# SAMV71_Xplained_Ultra_Power_Supply.net
KiCad netlist of a schematic drawn in Altium Designer
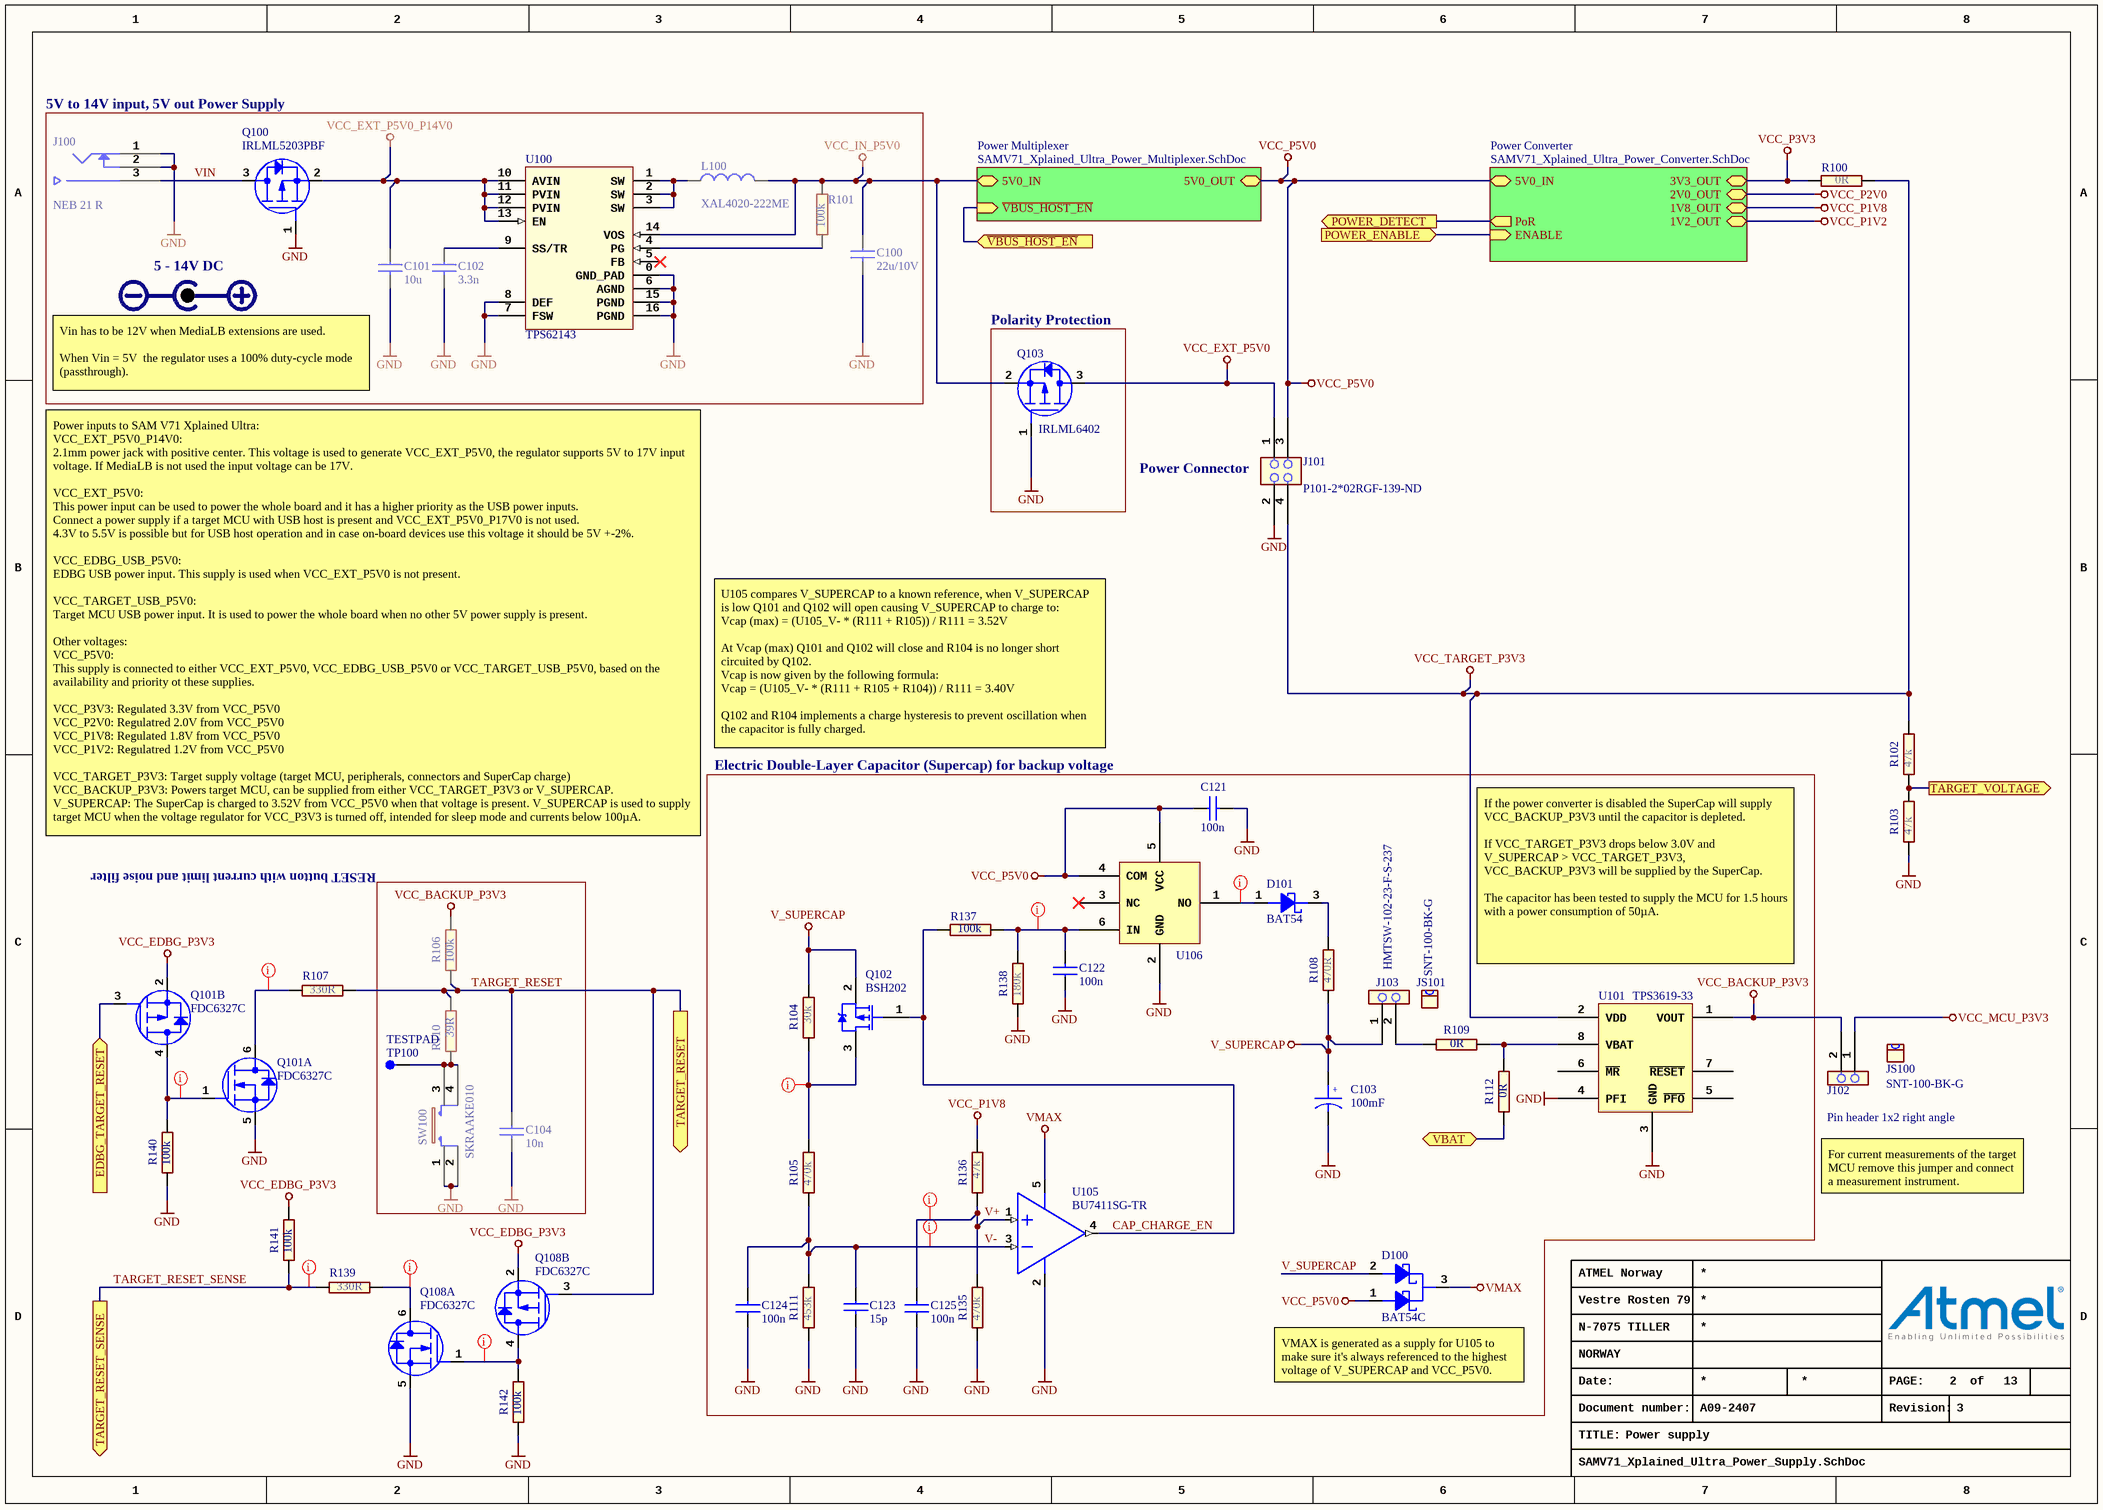
[diagram p0: SAMV71_Xplained_Ultra_Power_Supply.SchDoc]

(export (version "E")
  (design (tool "Eeschema 10.0.6"))
  (components
    (comp (ref "C100")
      (value "22u/10V")
      (footprint "AP1-00003")
      (description "Ceramic capacitor, SMD 0805, X5R, 10V, Â±20%")
      (fields (field (name "MANUFACTURER") "tdk") (field (name "MPN") "C2012X5R1A226M/0.85"))
      (libsource (lib "AltiumDbLib") (part "CAP-NONPOL"))
    )
    (comp (ref "C101")
      (value "10u")
      (footprint "AP1-00003")
      (description "Ceramic capacitor, SMD 0805, X5R, 25V, Â±10%")
      (fields (field (name "TOLERANCE") "Â±10%") (field (name "MANUFACTURER") "Murata"))
      (libsource (lib "AltiumDbLib") (part "CAP-NONPOL"))
    )
    (comp (ref "C102")
      (value "3.3n")
      (footprint "AP1-00001")
      (description "Ceramic capacitor, SMD 0402, X7R, 25V, +/-10%")
      (fields (field (name "TOLERANCE") "25V, +/-10%"))
      (libsource (lib "AltiumDbLib") (part "CAP-NONPOL"))
    )
    (comp (ref "C103")
      (value "100mF")
      (footprint "AP1-00122")
      (description "Electric Double-Layer (Supercapacitor), 100mF, SMD, 10.5mm diameter, 25Î© ESR")
      (fields (field (name "TOLERANCE") "-20/+80%") (field (name "MANUFACTURER") "Kemet"))
      (libsource (lib "AltiumDbLib") (part "CAP-POL"))
    )
    (comp (ref "C104")
      (value "10n")
      (footprint "AP1-00053")
      (description "Ceramic capacitor, SMD 0402, X7R, 25V, +/-10%")
      (fields (field (name "TOLERANCE") "25V, +/-10%"))
      (libsource (lib "AltiumDbLib") (part "CAP-NONPOL"))
    )
    (comp (ref "C121")
      (value "100n")
      (footprint "AP1-00001")
      (description "Ceramic capacitor, SMD 0402, X7R, 16V, +/-10%")
      (fields (field (name "TOLERANCE") "16V, +/-10%") (field (name "MANUFACTURER") "Kemet"))
      (libsource (lib "AltiumDbLib") (part "CAP-NONPOL"))
    )
    (comp (ref "C122")
      (value "100n")
      (footprint "AP1-00053")
      (description "Ceramic capacitor, SMD 0402, X7R, 16V, +/-10%")
      (fields (field (name "TOLERANCE") "16V, +/-10%") (field (name "MANUFACTURER") "Kemet"))
      (libsource (lib "AltiumDbLib") (part "CAP-NONPOL"))
    )
    (comp (ref "C123")
      (value "15p")
      (footprint "AP1-00001")
      (description "Ceramic capacitor, SMD 0402, NP0, 50V, +/-5%")
      (fields (field (name "TOLERANCE") "50V, +/-5%"))
      (libsource (lib "AltiumDbLib") (part "CAP-NONPOL"))
    )
    (comp (ref "C124")
      (value "100n")
      (footprint "AP1-00001")
      (description "Ceramic capacitor, SMD 0402, X7R, 16V, +/-10%")
      (fields (field (name "TOLERANCE") "16V, +/-10%") (field (name "MANUFACTURER") "Kemet"))
      (libsource (lib "AltiumDbLib") (part "CAP-NONPOL"))
    )
    (comp (ref "C125")
      (value "100n")
      (footprint "AP1-00001")
      (description "Ceramic capacitor, SMD 0402, X7R, 16V, +/-10%")
      (fields (field (name "TOLERANCE") "16V, +/-10%") (field (name "MANUFACTURER") "Kemet"))
      (libsource (lib "AltiumDbLib") (part "CAP-NONPOL"))
    )
    (comp (ref "D100")
      (value "BAT54C")
      (footprint "AP5-00002")
      (description "Schottky double Diodes, NXP, SOT23-3")
      (fields (field (name "MANUFACTURER") "NXP"))
      (libsource (lib "AltiumDbLib") (part "DUAL_SCHOTTKY_123"))
    )
    (comp (ref "D101")
      (value "BAT54")
      (footprint "AP4-00007")
      (fields (field (name "MANUFACTURER") "Philips"))
      (libsource (lib "AltiumDbLib") (part "SCHOTTKY_SMD_31"))
    )
    (comp (ref "J100")
      (value "NEB 21 R")
      (footprint "AP8-00853")
      (description "Through hole DC jack 2.1mm, 12V, 3A")
      (fields (field (name "MANUFACTURER") "Lumberg"))
      (libsource (lib "AltiumDbLib") (part "DC_JACK"))
    )
    (comp (ref "J101")
      (value "P101-2*02RGF-139-ND")
      (footprint "AP8-00628")
      (description "Pin header, 2x2, Right Angle, 2.54mm, THT, Pin In Paste")
      (fields (field (name "MANUFACTURER") "Pro-data International Corp"))
      (libsource (lib "AltiumDbLib") (part "HEADER 2x2"))
    )
    (comp (ref "J102")
      (value "Pin header 1x2 right angle")
      (footprint "AP8-00367")
      (description "1x2 pin header, right angle, 2.54 mm pitch, through-hole")
      (fields (field (name "MANUFACTURER") "Pro-data International Corp") (field (name "MPN") "2213R-2G"))
      (libsource (lib "") (part "HEADER 1x2_1"))
    )
    (comp (ref "J103")
      (value "HMTSW-102-23-F-S-237")
      (footprint "AP8-00733")
      (description "1x2 pin header, 2.54mm pitch, Pin-in-Paste THM")
      (fields (field (name "MANUFACTURER") "SAMTEC"))
      (libsource (lib "AltiumDbLib") (part "HEADER 1x2"))
    )
    (comp (ref "JS100")
      (value "SNT-100-BK-G")
      (footprint "AP8-00525")
      (description "Jumper cap for 2.54mm pinheader")
      (fields (field (name "MANUFACTURER") "SAMTEC"))
      (libsource (lib "AltiumDbLib") (part "JUMPER_CAP"))
    )
    (comp (ref "JS101")
      (value "SNT-100-BK-G")
      (footprint "AP8-00525")
      (description "Jumper cap for 2.54mm pinheader")
      (fields (field (name "MANUFACTURER") "SAMTEC"))
      (libsource (lib "AltiumDbLib") (part "JUMPER_CAP"))
    )
    (comp (ref "L100")
      (value "XAL4020-222ME")
      (footprint "AP3-00119")
      (description "2.2ÂµH Shielded Power Inductor, 4x4x2mm, Isat=5.6A , Irms=4.0A , DCR=35.2mÎ©")
      (fields (field (name "TOLERANCE") "20%") (field (name "MANUFACTURER") "Coilcraft"))
      (libsource (lib "AltiumDbLib") (part "INDUCTOR"))
    )
    (comp (ref "Q100")
      (value "IRLML5203PBF")
      (footprint "AP5-00002")
      (fields (field (name "MANUFACTURER") "International Rectifier"))
      (libsource (lib "AltiumDbLib") (part "MOSFET_P_GSD"))
    )
    (comp (ref "Q101")
      (value "FDC6327C")
      (footprint "AP5-00008")
      (fields (field (name "MANUFACTURER") "Fairchild") (field (name "Comment") "Farnell no: 9844856"))
      (libsource (lib "AltiumDbLib") (part "DUAL_NP_G1S2G2D2S1D1"))
    )
    (comp (ref "Q102")
      (value "BSH202")
      (footprint "AP4-00018")
      (description "P-channel Power MOSFET,30V, 520mA continuous drain current")
      (fields (field (name "MANUFACTURER") "NXP"))
      (libsource (lib "AltiumDbLib") (part "BSH202"))
    )
    (comp (ref "Q103")
      (value "IRLML6402")
      (footprint "AP5-00002")
      (description "P-ch. MOSFET. -30V, -3.7A continuous,RDS(ON)=0.05Ohm@VGS=-4,5V, RDS(ON)=0.08Ohm@VGS=-2.5V")
      (fields (field (name "MANUFACTURER") "International Rectifier") (field (name "MPN") "IRLML6402PBF"))
      (libsource (lib "AltiumDbLib") (part "MOSFET_P_GSD"))
    )
    (comp (ref "Q108")
      (value "FDC6327C")
      (footprint "AP5-00008")
      (fields (field (name "MANUFACTURER") "Fairchild") (field (name "Comment") "Farnell no: 9844856"))
      (libsource (lib "AltiumDbLib") (part "DUAL_NP_G1S2G2D2S1D1"))
    )
    (comp (ref "R100")
      (value "0R")
      (footprint "AP2-00000")
      (description "Thick film resistor, SMD 0402, 1/16W, 1%")
      (fields (field (name "TOLERANCE") "1 %") (field (name "MANUFACTURER") "(n/a)"))
      (libsource (lib "") (part "R2_1"))
    )
    (comp (ref "R101")
      (value "100k")
      (footprint "AP2-00000")
      (description "Thick film resistor, SMD 0402, 1/16W, 1%")
      (fields (field (name "TOLERANCE") "1 %"))
      (libsource (lib "") (part "R2_4"))
    )
    (comp (ref "R102")
      (value "47k")
      (footprint "AP2-00000")
      (description "Thick film resistor, SMD 0402, 1/16W, 1%")
      (fields (field (name "TOLERANCE") "1 %"))
      (libsource (lib "") (part "R2_3"))
    )
    (comp (ref "R103")
      (value "47k")
      (footprint "AP2-00000")
      (description "Thick film resistor, SMD 0402, 1/16W, 1%")
      (fields (field (name "TOLERANCE") "1 %"))
      (libsource (lib "") (part "R2_3"))
    )
    (comp (ref "R104")
      (value "30k")
      (footprint "AP2-00000")
      (description "Thick film resistor, SMD 0402, 1/16W, 1%")
      (fields (field (name "TOLERANCE") "1 %"))
      (libsource (lib "AltiumDbLib") (part "R2"))
    )
    (comp (ref "R105")
      (value "470k")
      (footprint "AP2-00000")
      (description "Thick film resistor, SMD 0402, 1/16W, 1%")
      (fields (field (name "TOLERANCE") "1 %"))
      (libsource (lib "AltiumDbLib") (part "R2"))
    )
    (comp (ref "R106")
      (value "100k")
      (footprint "AP2-00011")
      (description "Thick film resistor, SMD 0402, 1/16W, 1%")
      (fields (field (name "TOLERANCE") "1 %"))
      (libsource (lib "AltiumDbLib") (part "R2"))
    )
    (comp (ref "R107")
      (value "330R")
      (footprint "AP2-00011")
      (description "Thick film resistor, SMD 0402, 1/16W, 1%")
      (fields (field (name "TOLERANCE") "1 %"))
      (libsource (lib "") (part "R2_1"))
    )
    (comp (ref "R108")
      (value "470R")
      (footprint "AP2-00000")
      (description "Thick film resistor, SMD 0402, 1/16W, 1%")
      (fields (field (name "TOLERANCE") "1 %"))
      (libsource (lib "") (part "R2_4"))
    )
    (comp (ref "R109")
      (value "0R")
      (footprint "AP2-00000")
      (description "RES 0.0 OHM 1/16W 0402 SMD")
      (fields (field (name "TOLERANCE") "1 %") (field (name "MANUFACTURER") "(n/a)"))
      (libsource (lib "") (part "R2_1"))
    )
    (comp (ref "R110")
      (value "39R")
      (footprint "AP2-00011")
      (description "Thick film resistor, SMD 0402, 1/16W, 1%")
      (fields (field (name "TOLERANCE") "1 %"))
      (libsource (lib "") (part "R2_2"))
    )
    (comp (ref "R111")
      (value "453k")
      (footprint "AP2-00000")
      (description "Thick film resistor, SMD 0402, 1/16W, 1%")
      (fields (field (name "TOLERANCE") "1 %"))
      (libsource (lib "AltiumDbLib") (part "R2"))
    )
    (comp (ref "R112")
      (value "0R")
      (footprint "AP2-00000")
      (description "RES 0.0 OHM 1/16W 0402 SMD")
      (fields (field (name "TOLERANCE") "1 %") (field (name "MANUFACTURER") "(n/a)"))
      (libsource (lib "AltiumDbLib") (part "R2"))
    )
    (comp (ref "R135")
      (value "470k")
      (footprint "AP2-00000")
      (description "Thick film resistor, SMD 0402, 1/16W, 1%")
      (fields (field (name "TOLERANCE") "1 %"))
      (libsource (lib "AltiumDbLib") (part "R2"))
    )
    (comp (ref "R136")
      (value "47k")
      (footprint "AP2-00000")
      (description "Thick film resistor, SMD 0402, 1/16W, 1%")
      (fields (field (name "TOLERANCE") "1 %"))
      (libsource (lib "AltiumDbLib") (part "R2"))
    )
    (comp (ref "R137")
      (value "100k")
      (footprint "AP2-00011")
      (description "Thick film resistor, SMD 0402, 1/16W, 1%")
      (fields (field (name "TOLERANCE") "1 %"))
      (libsource (lib "") (part "R2_1"))
    )
    (comp (ref "R138")
      (value "180k")
      (footprint "AP2-00011")
      (description "Thick film resistor, SMD 0402, 1/16W, 1%")
      (fields (field (name "TOLERANCE") "1 %"))
      (libsource (lib "AltiumDbLib") (part "R2"))
    )
    (comp (ref "R139")
      (value "330R")
      (footprint "AP2-00011")
      (description "Thick film resistor, SMD 0402, 1/16W, 1%")
      (fields (field (name "TOLERANCE") "1 %"))
      (libsource (lib "") (part "R2_1"))
    )
    (comp (ref "R140")
      (value "100k")
      (footprint "AP2-00011")
      (description "Thick film resistor, SMD 0402, 1/16W, 1%")
      (fields (field (name "TOLERANCE") "1 %"))
      (libsource (lib "AltiumDbLib") (part "R2"))
    )
    (comp (ref "R141")
      (value "100k")
      (footprint "AP2-00011")
      (description "Thick film resistor, SMD 0402, 1/16W, 1%")
      (fields (field (name "TOLERANCE") "1 %"))
      (libsource (lib "AltiumDbLib") (part "R2"))
    )
    (comp (ref "R142")
      (value "100k")
      (footprint "AP2-00011")
      (description "Thick film resistor, SMD 0402, 1/16W, 1%")
      (fields (field (name "TOLERANCE") "1 %"))
      (libsource (lib "AltiumDbLib") (part "R2"))
    )
    (comp (ref "SW100")
      (value "SKRAAKE010")
      (footprint "AP8-00137")
      (description "6.2x6.2 mm SMD tact switch, same as A08-0091 but less force is needed")
      (fields
        (field (name "MANUFACTURER") "ALPS")
        (field (name "Comment") "Can be ordered in low volumes from Mouser")
      )
      (libsource (lib "AltiumDbLib") (part "PUSHBUTTON1"))
    )
    (comp (ref "TP100")
      (value "TESTPAD")
      (footprint "AP8-00010")
      (description "Single SMD testpad")
      (libsource (lib "AltiumDbLib") (part "TESTPOINT"))
    )
    (comp (ref "U100")
      (value "TPS62143")
      (footprint "AP6-00313")
      (description "5V to 17V in, 5V 2A out, Step-Down Converter")
      (fields (field (name "MANUFACTURER") "Texas Instruments") (field (name "MPN") "TPS62143RGTR"))
      (libsource (lib "AltiumDbLib") (part "TPS62143"))
    )
    (comp (ref "U101")
      (value "TPS3619-33")
      (footprint "AP6-00382")
      (description "Backup battery supervisors for RAM retention")
      (fields (field (name "MANUFACTURER") "Texas Instruments") (field (name "MPN") "TPS3619-33DGK"))
      (libsource (lib "AltiumDbLib") (part "TPS3619"))
    )
    (comp (ref "U105")
      (value "BU7411SG-TR")
      (footprint "AP6-00087")
      (description "Single, Low Voltage (1.6-5.5V), Low Power (0.35ÂµA), low cost")
      (fields (field (name "MANUFACTURER") "ROHM"))
      (libsource (lib "AltiumDbLib") (part "LMV321M5"))
    )
    (comp (ref "U106")
      (value "~")
      (footprint "AP6-00056")
      (description "1.65V to 5.5V SPDT Analog switch")
      (fields (field (name "MANUFACTURER") "Texas Instruments") (field (name "MPN") "TS5A3160DBVR"))
      (libsource (lib "AltiumDbLib") (part "TS5A3160"))
    )
  )
  (nets
    (net (code "1") (name "/CAP_CHARGE_EN") (class "Default")
      (node (ref "Q102") (pin "1") (pinfunction "G_1") (pintype "passive"))
      (node (ref "R137") (pin "1") (pinfunction "1_1") (pintype "passive"))
      (node (ref "U105") (pin "4") (pinfunction "OUT_4") (pintype "output"))
    )
    (net (code "2") (name "/EDBG_TARGET_RESET") (class "Default")
      (node (ref "Q101") (pin "3") (pinfunction "G_3") (pintype "passive"))
    )
    (net (code "5") (name "/TARGET_RESET") (class "Default")
      (node (ref "C104") (pin "1") (pinfunction "1_1") (pintype "passive"))
      (node (ref "Q108") (pin "3") (pinfunction "G_3") (pintype "passive"))
      (node (ref "R106") (pin "1") (pinfunction "1_1") (pintype "passive"))
      (node (ref "R107") (pin "2") (pinfunction "2_2") (pintype "passive"))
      (node (ref "R110") (pin "2") (pinfunction "2_2") (pintype "passive"))
    )
    (net (code "6") (name "/TARGET_RESET_SENSE") (class "Default")
      (node (ref "R139") (pin "1") (pinfunction "1_1") (pintype "passive"))
      (node (ref "R141") (pin "1") (pinfunction "1_1") (pintype "passive"))
    )
    (net (code "7") (name "/TARGET_VOLTAGE") (class "Default")
      (node (ref "R102") (pin "1") (pinfunction "1_1") (pintype "passive"))
      (node (ref "R103") (pin "2") (pinfunction "2_2") (pintype "passive"))
    )
    (net (code "8") (name "/V+") (class "Default")
      (node (ref "C125") (pin "2") (pinfunction "2_2") (pintype "passive"))
      (node (ref "R135") (pin "2") (pinfunction "2_2") (pintype "passive"))
      (node (ref "R136") (pin "1") (pinfunction "1_1") (pintype "passive"))
      (node (ref "U105") (pin "1") (pinfunction "IN+_1") (pintype "input"))
    )
    (net (code "9") (name "/V-") (class "Default")
      (node (ref "C123") (pin "1") (pinfunction "1_1") (pintype "passive"))
      (node (ref "C124") (pin "2") (pinfunction "2_2") (pintype "passive"))
      (node (ref "R105") (pin "1") (pinfunction "1_1") (pintype "passive"))
      (node (ref "R111") (pin "2") (pinfunction "2_2") (pintype "passive"))
      (node (ref "U105") (pin "3") (pinfunction "IN-_3") (pintype "input"))
    )
    (net (code "10") (name "/VBAT") (class "Default")
      (node (ref "R112") (pin "1") (pinfunction "1_1") (pintype "passive"))
    )
    (net (code "11") (name "/VIN") (class "Default")
      (node (ref "J100") (pin "3") (pinfunction "3_3") (pintype "passive"))
      (node (ref "Q100") (pin "3") (pinfunction "D_3") (pintype "passive"))
    )
    (net (code "13") (name "GND") (class "Default")
      (node (ref "C100") (pin "2") (pinfunction "2_2") (pintype "passive"))
      (node (ref "C101") (pin "2") (pinfunction "2_2") (pintype "passive"))
      (node (ref "C102") (pin "2") (pinfunction "2_2") (pintype "passive"))
      (node (ref "C103") (pin "2") (pinfunction "2_2") (pintype "passive"))
      (node (ref "C104") (pin "2") (pinfunction "2_2") (pintype "passive"))
      (node (ref "C121") (pin "2") (pinfunction "2_2") (pintype "passive"))
      (node (ref "C122") (pin "1") (pinfunction "1_1") (pintype "passive"))
      (node (ref "C123") (pin "2") (pinfunction "2_2") (pintype "passive"))
      (node (ref "C124") (pin "1") (pinfunction "1_1") (pintype "passive"))
      (node (ref "C125") (pin "1") (pinfunction "1_1") (pintype "passive"))
      (node (ref "J100") (pin "1") (pinfunction "1_1") (pintype "passive"))
      (node (ref "J100") (pin "2") (pinfunction "2_2") (pintype "passive"))
      (node (ref "J101") (pin "2") (pinfunction "2_2") (pintype "passive"))
      (node (ref "Q100") (pin "1") (pinfunction "G_1") (pintype "passive"))
      (node (ref "Q101") (pin "5") (pinfunction "S_5") (pintype "passive"))
      (node (ref "Q103") (pin "1") (pinfunction "G_1") (pintype "passive"))
      (node (ref "Q108") (pin "5") (pinfunction "S_5") (pintype "passive"))
      (node (ref "R103") (pin "1") (pinfunction "1_1") (pintype "passive"))
      (node (ref "R111") (pin "1") (pinfunction "1_1") (pintype "passive"))
      (node (ref "R135") (pin "1") (pinfunction "1_1") (pintype "passive"))
      (node (ref "R138") (pin "1") (pinfunction "1_1") (pintype "passive"))
      (node (ref "R140") (pin "1") (pinfunction "1_1") (pintype "passive"))
      (node (ref "R142") (pin "1") (pinfunction "1_1") (pintype "passive"))
      (node (ref "SW100") (pin "1") (pinfunction "1_1") (pintype "passive"))
      (node (ref "SW100") (pin "2") (pinfunction "2_2") (pintype "passive"))
      (node (ref "U100") (pin "0") (pinfunction "GND_PAD_0") (pintype "passive"))
      (node (ref "U100") (pin "15") (pinfunction "PGND_15") (pintype "power_in"))
      (node (ref "U100") (pin "16") (pinfunction "PGND_16") (pintype "power_in"))
      (node (ref "U100") (pin "6") (pinfunction "AGND_6") (pintype "power_in"))
      (node (ref "U100") (pin "7") (pinfunction "FSW_7") (pintype "power_in"))
      (node (ref "U100") (pin "8") (pinfunction "DEF_8") (pintype "power_in"))
      (node (ref "U101") (pin "3") (pinfunction "GND_3") (pintype "passive"))
      (node (ref "U101") (pin "4") (pinfunction "PFI_4") (pintype "passive"))
      (node (ref "U105") (pin "2") (pinfunction "GND_2") (pintype "power_in"))
      (node (ref "U106") (pin "2") (pinfunction "GND_2") (pintype "passive"))
    )
    (net (code "14") (name "Net-(D101-ANODE)") (class "Default")
      (node (ref "D101") (pin "1") (pinfunction "ANODE_1") (pintype "passive"))
      (node (ref "U106") (pin "1") (pinfunction "NO_1") (pintype "passive"))
    )
    (net (code "15") (name "Net-(D101-CATHODE)") (class "Default")
      (node (ref "D101") (pin "3") (pinfunction "CATHODE_3") (pintype "passive"))
      (node (ref "R108") (pin "1") (pinfunction "1_1") (pintype "passive"))
    )
    (net (code "16") (name "Net-(J103-Pad2)") (class "Default")
      (node (ref "J103") (pin "2") (pinfunction "2_2") (pintype "passive"))
      (node (ref "R109") (pin "1") (pinfunction "1_1") (pintype "passive"))
    )
    (net (code "17") (name "Net-(L100-Pad1)") (class "Default")
      (node (ref "L100") (pin "1") (pinfunction "1_1") (pintype "passive"))
      (node (ref "U100") (pin "1") (pinfunction "SW_1") (pintype "power_in"))
      (node (ref "U100") (pin "2") (pinfunction "SW_2") (pintype "power_in"))
      (node (ref "U100") (pin "3") (pinfunction "SW_3") (pintype "power_in"))
    )
    (net (code "18") (name "Net-(Q101A-D)") (class "Default")
      (node (ref "Q101") (pin "6") (pinfunction "D_6") (pintype "passive"))
      (node (ref "R107") (pin "1") (pinfunction "1_1") (pintype "passive"))
    )
    (net (code "19") (name "Net-(Q101A-G)") (class "Default")
      (node (ref "Q101") (pin "1") (pinfunction "G_1") (pintype "passive"))
      (node (ref "Q101") (pin "4") (pinfunction "D_4") (pintype "passive"))
      (node (ref "R140") (pin "2") (pinfunction "2_2") (pintype "passive"))
    )
    (net (code "20") (name "Net-(Q102-D)") (class "Default")
      (node (ref "Q102") (pin "3") (pinfunction "D_3") (pintype "passive"))
      (node (ref "R104") (pin "1") (pinfunction "1_1") (pintype "passive"))
      (node (ref "R105") (pin "2") (pinfunction "2_2") (pintype "passive"))
    )
    (net (code "21") (name "Net-(Q108A-D)") (class "Default")
      (node (ref "Q108") (pin "6") (pinfunction "D_6") (pintype "passive"))
      (node (ref "R139") (pin "2") (pinfunction "2_2") (pintype "passive"))
    )
    (net (code "22") (name "Net-(Q108A-G)") (class "Default")
      (node (ref "Q108") (pin "1") (pinfunction "G_1") (pintype "passive"))
      (node (ref "Q108") (pin "4") (pinfunction "D_4") (pintype "passive"))
      (node (ref "R142") (pin "2") (pinfunction "2_2") (pintype "passive"))
    )
    (net (code "23") (name "Net-(R110-Pad1)") (class "Default")
      (node (ref "R110") (pin "1") (pinfunction "1_1") (pintype "passive"))
      (node (ref "SW100") (pin "3") (pinfunction "3_3") (pintype "passive"))
      (node (ref "SW100") (pin "4") (pinfunction "4_4") (pintype "passive"))
      (node (ref "TP100") (pin "1") (pinfunction "1_1") (pintype "passive"))
    )
    (net (code "24") (name "Net-(U100-PG)") (class "Default")
      (node (ref "R101") (pin "2") (pinfunction "2_2") (pintype "passive"))
      (node (ref "U100") (pin "4") (pinfunction "PG_4") (pintype "input"))
    )
    (net (code "25") (name "Net-(U100-SS{slash}TR)") (class "Default")
      (node (ref "C102") (pin "1") (pinfunction "1_1") (pintype "passive"))
      (node (ref "U100") (pin "9") (pinfunction "SS/TR_9") (pintype "passive"))
    )
    (net (code "26") (name "Net-(U101-VBAT)") (class "Default")
      (node (ref "R109") (pin "2") (pinfunction "2_2") (pintype "passive"))
      (node (ref "R112") (pin "2") (pinfunction "2_2") (pintype "passive"))
      (node (ref "U101") (pin "8") (pinfunction "VBAT_8") (pintype "passive"))
    )
    (net (code "27") (name "Net-(U106-IN)") (class "Default")
      (node (ref "C122") (pin "2") (pinfunction "2_2") (pintype "passive"))
      (node (ref "R137") (pin "2") (pinfunction "2_2") (pintype "passive"))
      (node (ref "R138") (pin "2") (pinfunction "2_2") (pintype "passive"))
      (node (ref "U106") (pin "6") (pinfunction "IN_6") (pintype "passive"))
    )
    (net (code "28") (name "VCC_BACKUP_P3V3") (class "Default")
      (node (ref "J102") (pin "2") (pinfunction "2_2") (pintype "passive"))
      (node (ref "R106") (pin "2") (pinfunction "2_2") (pintype "passive"))
      (node (ref "U101") (pin "1") (pinfunction "VOUT_1") (pintype "passive"))
    )
    (net (code "29") (name "VCC_EDBG_P3V3") (class "Default")
      (node (ref "Q101") (pin "2") (pinfunction "S_2") (pintype "passive"))
      (node (ref "Q108") (pin "2") (pinfunction "S_2") (pintype "passive"))
      (node (ref "R141") (pin "2") (pinfunction "2_2") (pintype "passive"))
    )
    (net (code "30") (name "VCC_EXT_P5V0") (class "Default")
      (node (ref "J101") (pin "1") (pinfunction "1_1") (pintype "passive"))
      (node (ref "Q103") (pin "3") (pinfunction "D_3") (pintype "passive"))
    )
    (net (code "31") (name "VCC_EXT_P5V0_P14V0") (class "Default")
      (node (ref "C101") (pin "1") (pinfunction "1_1") (pintype "passive"))
      (node (ref "Q100") (pin "2") (pinfunction "S_2") (pintype "passive"))
      (node (ref "U100") (pin "10") (pinfunction "AVIN_10") (pintype "power_in"))
      (node (ref "U100") (pin "11") (pinfunction "PVIN_11") (pintype "power_in"))
      (node (ref "U100") (pin "12") (pinfunction "PVIN_12") (pintype "power_in"))
      (node (ref "U100") (pin "13") (pinfunction "EN_13") (pintype "input"))
    )
    (net (code "32") (name "VCC_IN_P5V0") (class "Default")
      (node (ref "C100") (pin "1") (pinfunction "1_1") (pintype "passive"))
      (node (ref "L100") (pin "2") (pinfunction "2_2") (pintype "passive"))
      (node (ref "Q103") (pin "2") (pinfunction "S_2") (pintype "passive"))
      (node (ref "R101") (pin "1") (pinfunction "1_1") (pintype "passive"))
      (node (ref "U100") (pin "14") (pinfunction "VOS_14") (pintype "input"))
    )
    (net (code "33") (name "VCC_MCU_P3V3") (class "Default")
      (node (ref "J102") (pin "1") (pinfunction "1_1") (pintype "passive"))
    )
    (net (code "35") (name "VCC_P1V8") (class "Default")
      (node (ref "R136") (pin "2") (pinfunction "2_2") (pintype "passive"))
    )
    (net (code "37") (name "VCC_P3V3") (class "Default")
      (node (ref "R100") (pin "1") (pinfunction "1_1") (pintype "passive"))
    )
    (net (code "38") (name "VCC_P5V0") (class "Default")
      (node (ref "C121") (pin "1") (pinfunction "1_1") (pintype "passive"))
      (node (ref "D100") (pin "1") (pinfunction "ANODE1_1") (pintype "passive"))
      (node (ref "J101") (pin "3") (pinfunction "3_3") (pintype "passive"))
      (node (ref "U106") (pin "4") (pinfunction "COM_4") (pintype "passive"))
      (node (ref "U106") (pin "5") (pinfunction "VCC_5") (pintype "passive"))
    )
    (net (code "39") (name "VCC_TARGET_P3V3") (class "Default")
      (node (ref "J101") (pin "4") (pinfunction "4_4") (pintype "passive"))
      (node (ref "R100") (pin "2") (pinfunction "2_2") (pintype "passive"))
      (node (ref "R102") (pin "2") (pinfunction "2_2") (pintype "passive"))
      (node (ref "U101") (pin "2") (pinfunction "VDD_2") (pintype "passive"))
    )
    (net (code "40") (name "VMAX") (class "Default")
      (node (ref "D100") (pin "3") (pinfunction "CATHODE_3") (pintype "passive"))
      (node (ref "U105") (pin "5") (pinfunction "VCC_5") (pintype "power_in"))
    )
    (net (code "41") (name "V_SUPERCAP") (class "Default")
      (node (ref "C103") (pin "1") (pinfunction "1_1") (pintype "passive"))
      (node (ref "D100") (pin "2") (pinfunction "ANODE2_2") (pintype "passive"))
      (node (ref "J103") (pin "1") (pinfunction "1_1") (pintype "passive"))
      (node (ref "Q102") (pin "2") (pinfunction "S_2") (pintype "passive"))
      (node (ref "R104") (pin "2") (pinfunction "2_2") (pintype "passive"))
      (node (ref "R108") (pin "2") (pinfunction "2_2") (pintype "passive"))
    )
    (net (code "42") (name "unconnected-(U100-FB-Pad5)") (class "Default")
      (node (ref "U100") (pin "5") (pinfunction "FB_5") (pintype "input+no_connect"))
    )
    (net (code "43") (name "unconnected-(U101-~{MR}-Pad6)") (class "Default")
      (node (ref "U101") (pin "6") (pinfunction "~{MR}_6") (pintype "passive"))
    )
    (net (code "44") (name "unconnected-(U101-~{PFO}-Pad5)") (class "Default")
      (node (ref "U101") (pin "5") (pinfunction "~{PFO}_5") (pintype "passive"))
    )
    (net (code "45") (name "unconnected-(U101-~{RESET}-Pad7)") (class "Default")
      (node (ref "U101") (pin "7") (pinfunction "~{RESET}_7") (pintype "passive"))
    )
    (net (code "46") (name "unconnected-(U106-NC-Pad3)") (class "Default")
      (node (ref "U106") (pin "3") (pinfunction "NC_3") (pintype "passive+no_connect"))
    )
  )
)
